# 05_-_Power_supply.net
KiCad netlist of a schematic drawn in Altium Designer
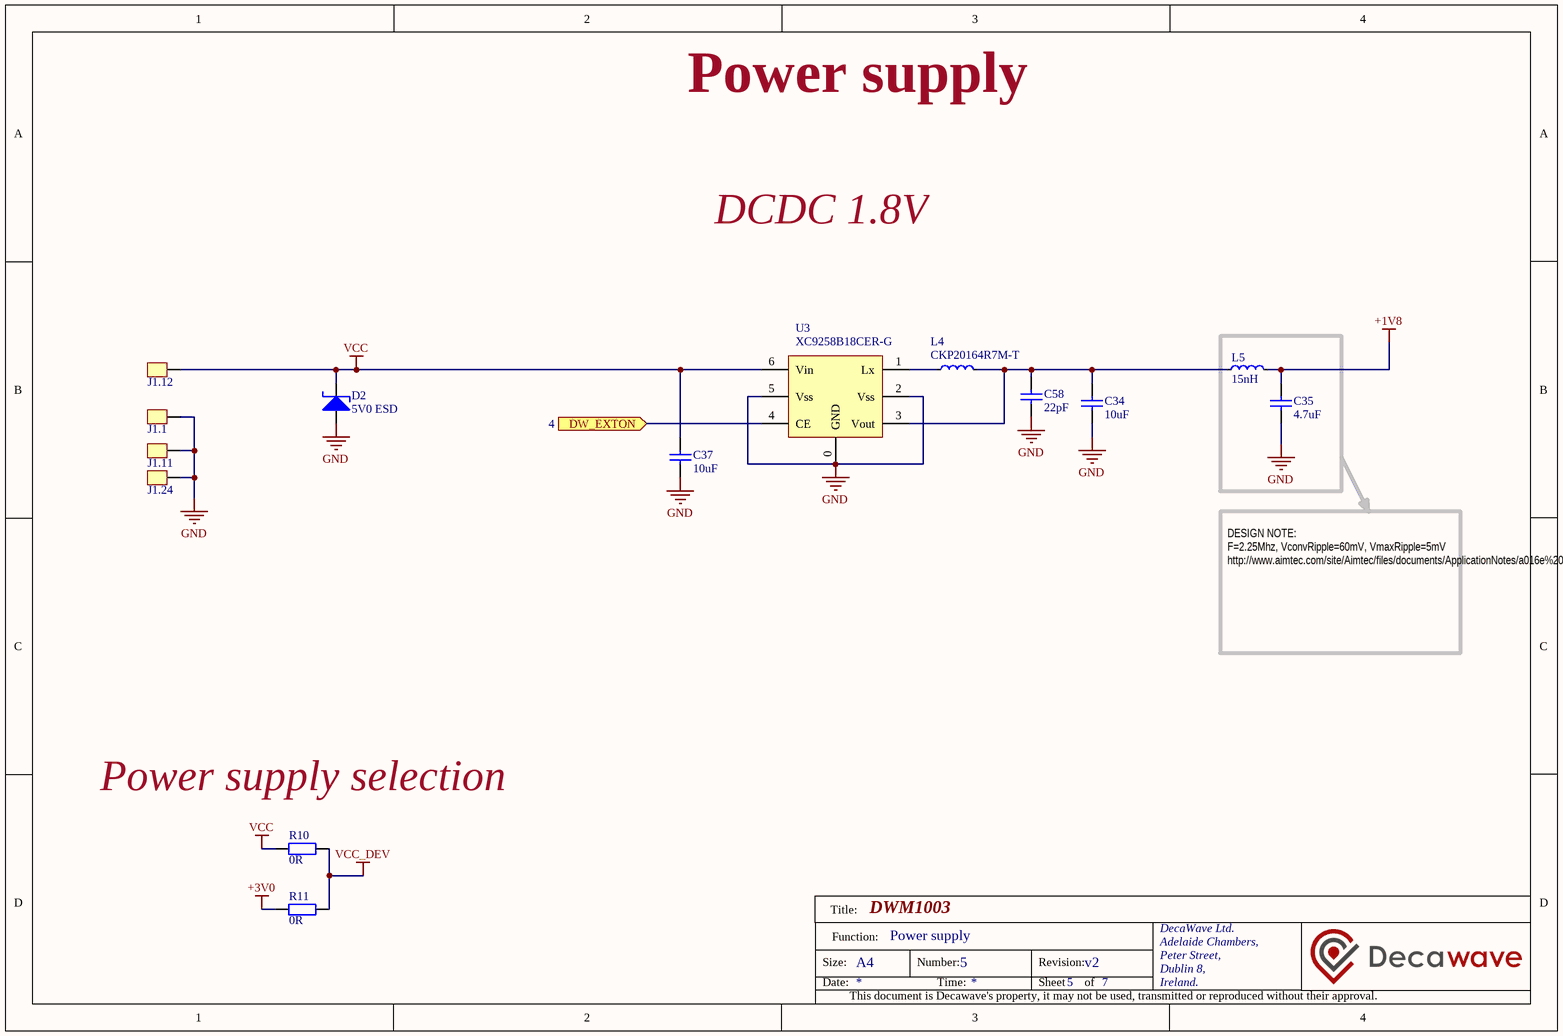
[diagram p0: [05] - Power supply.SchDoc]

(export (version "E")
  (design (tool "Eeschema 10.0.6"))
  (components
    (comp (ref "C34")
      (value "10uF")
      (footprint "C0603")
      (description "CAP CER 10UF 6.3V X5R 0603")
      (fields
        (field (name "MANUFACTURER") "Murata Electronics North America")
        (field (name "MANUFACTURER PART NUMBER") "GRM188R60J106ME47D")
      )
      (libsource (lib "drak_Library") (part "GRM188R60J106ME84D"))
    )
    (comp (ref "C35")
      (value "4.7uF")
      (footprint "C0603")
      (description "CAP CER 4.7UF 6.3V X5R 0603")
      (fields
        (field (name "MANUFACTURER") "SamSung")
        (field (name "MANUFACTURER PART NUMBER") "CL10A475KQ8NNN#")
      )
      (libsource (lib "Schlib1") (part "CL10A475KQ8NNN#"))
    )
    (comp (ref "C37")
      (value "10uF")
      (footprint "C0603")
      (description "CAP CER 10UF 6.3V X5R 0603")
      (fields
        (field (name "MANUFACTURER") "Murata Electronics North America")
        (field (name "MANUFACTURER PART NUMBER") "GRM188R60J106ME47D")
      )
      (libsource (lib "Schlib1") (part "CL10A475KQ8NNN#"))
    )
    (comp (ref "C58")
      (value "22pF")
      (footprint "C0201")
      (description "CAP CER 22PF 25V NP0 0201")
      (fields
        (field (name "MANUFACTURER") "Murata Electronics North America")
        (field (name "MANUFACTURER PART NUMBER") "GRM0335C1E220JA01D")
      )
      (libsource (lib "Schlib1") (part "GRM0335C1E100JA01D"))
    )
    (comp (ref "D2")
      (value "5V0 ESD")
      (footprint "DFN65P100X40-2N")
      (description "TVS DIODE 5VWM")
      (fields
        (field (name "MANUFACTURER") "Toshiba Semiconductor and Storage")
        (field (name "MANUFACTURER PART NUMBER") "DF2S6.2CT,L3F")
      )
      (libsource (lib "drak_Library") (part "DF2S6.2CT,L3F"))
    )
    (comp (ref "J1.1")
      (value "EDGE_PIN")
      (footprint "PCB_EDGE_1MM")
      (description "PCB Edge pin")
      (libsource (lib "DrakSchlib") (part "EDGE_PIN"))
    )
    (comp (ref "J1.11")
      (value "EDGE_PIN")
      (footprint "PCB_EDGE_1MM")
      (description "PCB Edge pin")
      (libsource (lib "DrakSchlib") (part "EDGE_PIN"))
    )
    (comp (ref "J1.12")
      (value "EDGE_PIN")
      (footprint "PCB_EDGE_1MM")
      (description "PCB Edge pin")
      (libsource (lib "DrakSchlib") (part "EDGE_PIN"))
    )
    (comp (ref "J1.24")
      (value "EDGE_PIN")
      (footprint "PCB_EDGE_1MM")
      (description "PCB Edge pin")
      (libsource (lib "DrakSchlib") (part "EDGE_PIN"))
    )
    (comp (ref "L4")
      (value "CKP20164R7M-T")
      (footprint "INDC2016X10N")
      (description "FIXED IND 2.2UH 1.2A 110 MOHM")
      (fields
        (field (name "MANUFACTURER") "TAIYO YUDEN")
        (field (name "MANUFACTURER PART NUMBER") "CKP20162R2M-T")
      )
      (libsource (lib "Schlib1") (part "CKP20162R2M-T"))
    )
    (comp (ref "L5")
      (value "15nH")
      (footprint "INDC1005X05N")
      (description "FIXED IND 15NH 320MA 460 MOHM")
      (fields
        (field (name "MANUFACTURER") "Taiyo Yuden")
        (field (name "MANUFACTURER PART NUMBER") "HK100515NJ-T")
      )
      (libsource (lib "Schlib1") (part "HK100515NJ-T"))
    )
    (comp (ref "R10")
      (value "0R")
      (footprint "R0201")
      (description "RES SMD 0.0OHM JUMPER 1/20W 0201")
      (fields
        (field (name "MANUFACTURER") "Yageo")
        (field (name "MANUFACTURER PART NUMBER") "RC0201JR-070RL")
      )
      (libsource (lib "drak_Library") (part "RC0201JR-070RL"))
    )
    (comp (ref "R11")
      (value "0R")
      (footprint "R0201")
      (description "RES SMD 0.0OHM JUMPER 1/20W 0201")
      (fields
        (field (name "MANUFACTURER") "Yageo")
        (field (name "MANUFACTURER PART NUMBER") "RC0201JR-070RL")
      )
      (libsource (lib "drak_Library") (part "RC0201JR-070RL"))
    )
    (comp (ref "U3")
      (value "XC9258B18CER-G")
      (footprint "USP-6C")
      (fields (field (name "MANUFACTURER") "Torex"))
      (libsource (lib "LGA12_LGA14_LIB") (part "XC9257/8"))
    )
  )
  (nets
    (net (code "1") (name "+1V8") (class "Default")
      (node (ref "C35") (pin "2") (pinfunction "2_2") (pintype "passive"))
      (node (ref "L5") (pin "2") (pinfunction "2_2") (pintype "passive"))
    )
    (net (code "2") (name "+3V0") (class "Default")
      (node (ref "R11") (pin "1") (pinfunction "1_1") (pintype "passive"))
    )
    (net (code "3") (name "/DW_EXTON") (class "Default")
      (node (ref "U3") (pin "4") (pinfunction "CE_4") (pintype "passive"))
    )
    (net (code "4") (name "GND") (class "Default")
      (node (ref "C34") (pin "1") (pinfunction "1_1") (pintype "passive"))
      (node (ref "C35") (pin "1") (pinfunction "1_1") (pintype "passive"))
      (node (ref "C37") (pin "1") (pinfunction "1_1") (pintype "passive"))
      (node (ref "C58") (pin "1") (pinfunction "1_1") (pintype "passive"))
      (node (ref "D2") (pin "A") (pinfunction "A_A") (pintype "passive"))
      (node (ref "J1.1") (pin "0") (pinfunction "0_0") (pintype "passive"))
      (node (ref "J1.11") (pin "0") (pinfunction "0_0") (pintype "passive"))
      (node (ref "J1.24") (pin "0") (pinfunction "0_0") (pintype "passive"))
      (node (ref "U3") (pin "0") (pinfunction "GND_0") (pintype "passive"))
      (node (ref "U3") (pin "2") (pinfunction "Vss_2") (pintype "passive"))
      (node (ref "U3") (pin "5") (pinfunction "Vss_5") (pintype "passive"))
    )
    (net (code "5") (name "Net-(U3-Lx)") (class "Default")
      (node (ref "L4") (pin "1") (pinfunction "1_1") (pintype "passive"))
      (node (ref "U3") (pin "1") (pinfunction "Lx_1") (pintype "passive"))
    )
    (net (code "6") (name "Net-(U3-Vout)") (class "Default")
      (node (ref "C34") (pin "2") (pinfunction "2_2") (pintype "passive"))
      (node (ref "C58") (pin "2") (pinfunction "2_2") (pintype "passive"))
      (node (ref "L4") (pin "2") (pinfunction "2_2") (pintype "passive"))
      (node (ref "L5") (pin "1") (pinfunction "1_1") (pintype "passive"))
      (node (ref "U3") (pin "3") (pinfunction "Vout_3") (pintype "passive"))
    )
    (net (code "7") (name "VCC") (class "Default")
      (node (ref "C37") (pin "2") (pinfunction "2_2") (pintype "passive"))
      (node (ref "D2") (pin "K") (pinfunction "K_K") (pintype "passive"))
      (node (ref "J1.12") (pin "0") (pinfunction "0_0") (pintype "passive"))
      (node (ref "R10") (pin "1") (pinfunction "1_1") (pintype "passive"))
      (node (ref "U3") (pin "6") (pinfunction "Vin_6") (pintype "passive"))
    )
    (net (code "8") (name "VCC_DEV") (class "Default")
      (node (ref "R10") (pin "2") (pinfunction "2_2") (pintype "passive"))
      (node (ref "R11") (pin "2") (pinfunction "2_2") (pintype "passive"))
    )
  )
)
